# Thermal_camera_1.net
KiCad netlist of a schematic drawn in Altium Designer
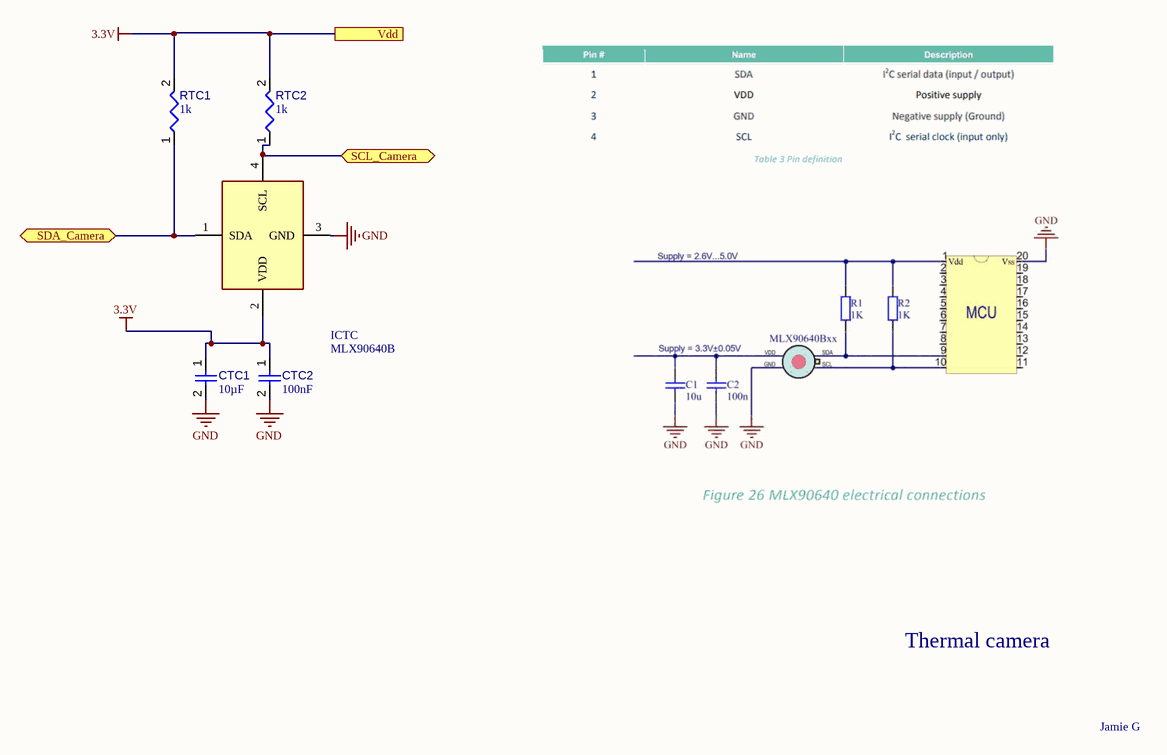
[diagram p0: Thermal camera_1.SchDoc]

(export (version "E")
  (design (tool "Eeschema 10.0.6"))
  (components
    (comp (ref "CTC1")
      (value "10µF")
      (footprint "CAPC0603(1608)100_L")
      (description "Chip Capacitor, 10µF +/-20%, 10V, 0603, Thickness 1 mm")
      (fields (field (name "TOLERANCE") "10%") (field (name "Comment") "Capacitor 10µF +/-20% 10V 0603"))
      (libsource (lib "Project Sunsat") (part "CAP-NP-2"))
    )
    (comp (ref "CTC2")
      (value "100nF")
      (footprint "CAPC0402(1005)60_L")
      (description "Chip Capacitor, 100nF +/-20%, 10V, 0402, Thickness 0.6 mm")
      (fields (field (name "TOLERANCE") "20%") (field (name "Comment") "Capacitor 100nF +/-20% 10V 0402"))
      (libsource (lib "Project Sunsat") (part "CAP-NP-2"))
    )
    (comp (ref "ICTC")
      (value "MLX90640B")
      (footprint "SamacSys:MLX90640ESFBAA000TU")
      (description "Integrated Circuit")
      (fields
        (field (name "MANUFACTURER_PART_NUMBER") "MLX90640ESF-BAA-000-SP")
        (field (name "MOUSER PART NUMBER") "482-MLX90640ESFBAASP")
      )
      (libsource (lib "*") (part "MLX90640ESF-BAA-000-SP"))
    )
    (comp (ref "RTC1")
      (value "1k")
      (footprint "RESC0402(1005)_L")
      (description "Chip Resistor, 1 kOhms, +/-5 %, 63 mW, -55 to 155 degC, 0402")
      (fields (field (name "TOLERANCE") "5%") (field (name "POWER") "63mW"))
      (libsource (lib "Project Sunsat") (part "RES-2"))
    )
    (comp (ref "RTC2")
      (value "1k")
      (footprint "RESC0402(1005)_L")
      (description "Chip Resistor, 1 kOhms, +/-5 %, 63 mW, -55 to 155 degC, 0402")
      (fields (field (name "TOLERANCE") "5%") (field (name "POWER") "63mW"))
      (libsource (lib "Project Sunsat") (part "RES-2"))
    )
  )
  (nets
    (net (code "1") (name "/SCL_Camera") (class "Default")
      (node (ref "ICTC") (pin "4") (pinfunction "SCL_4") (pintype "passive"))
      (node (ref "RTC2") (pin "1") (pinfunction "1_1") (pintype "passive"))
    )
    (net (code "2") (name "/SDA_Camera") (class "Default")
      (node (ref "ICTC") (pin "1") (pinfunction "SDA_1") (pintype "passive"))
      (node (ref "RTC1") (pin "1") (pinfunction "1_1") (pintype "passive"))
    )
    (net (code "3") (name "3.3V") (class "Default")
      (node (ref "CTC1") (pin "1") (pinfunction "1_1") (pintype "passive"))
      (node (ref "CTC2") (pin "1") (pinfunction "1_1") (pintype "passive"))
      (node (ref "ICTC") (pin "2") (pinfunction "VDD_2") (pintype "passive"))
      (node (ref "RTC1") (pin "2") (pinfunction "2_2") (pintype "passive"))
      (node (ref "RTC2") (pin "2") (pinfunction "2_2") (pintype "passive"))
    )
    (net (code "4") (name "GND") (class "Default")
      (node (ref "CTC1") (pin "2") (pinfunction "2_2") (pintype "passive"))
      (node (ref "CTC2") (pin "2") (pinfunction "2_2") (pintype "passive"))
      (node (ref "ICTC") (pin "3") (pinfunction "GND_3") (pintype "passive"))
    )
  )
)
